# M1103A.net
KiCad netlist of a schematic drawn in EAGLE
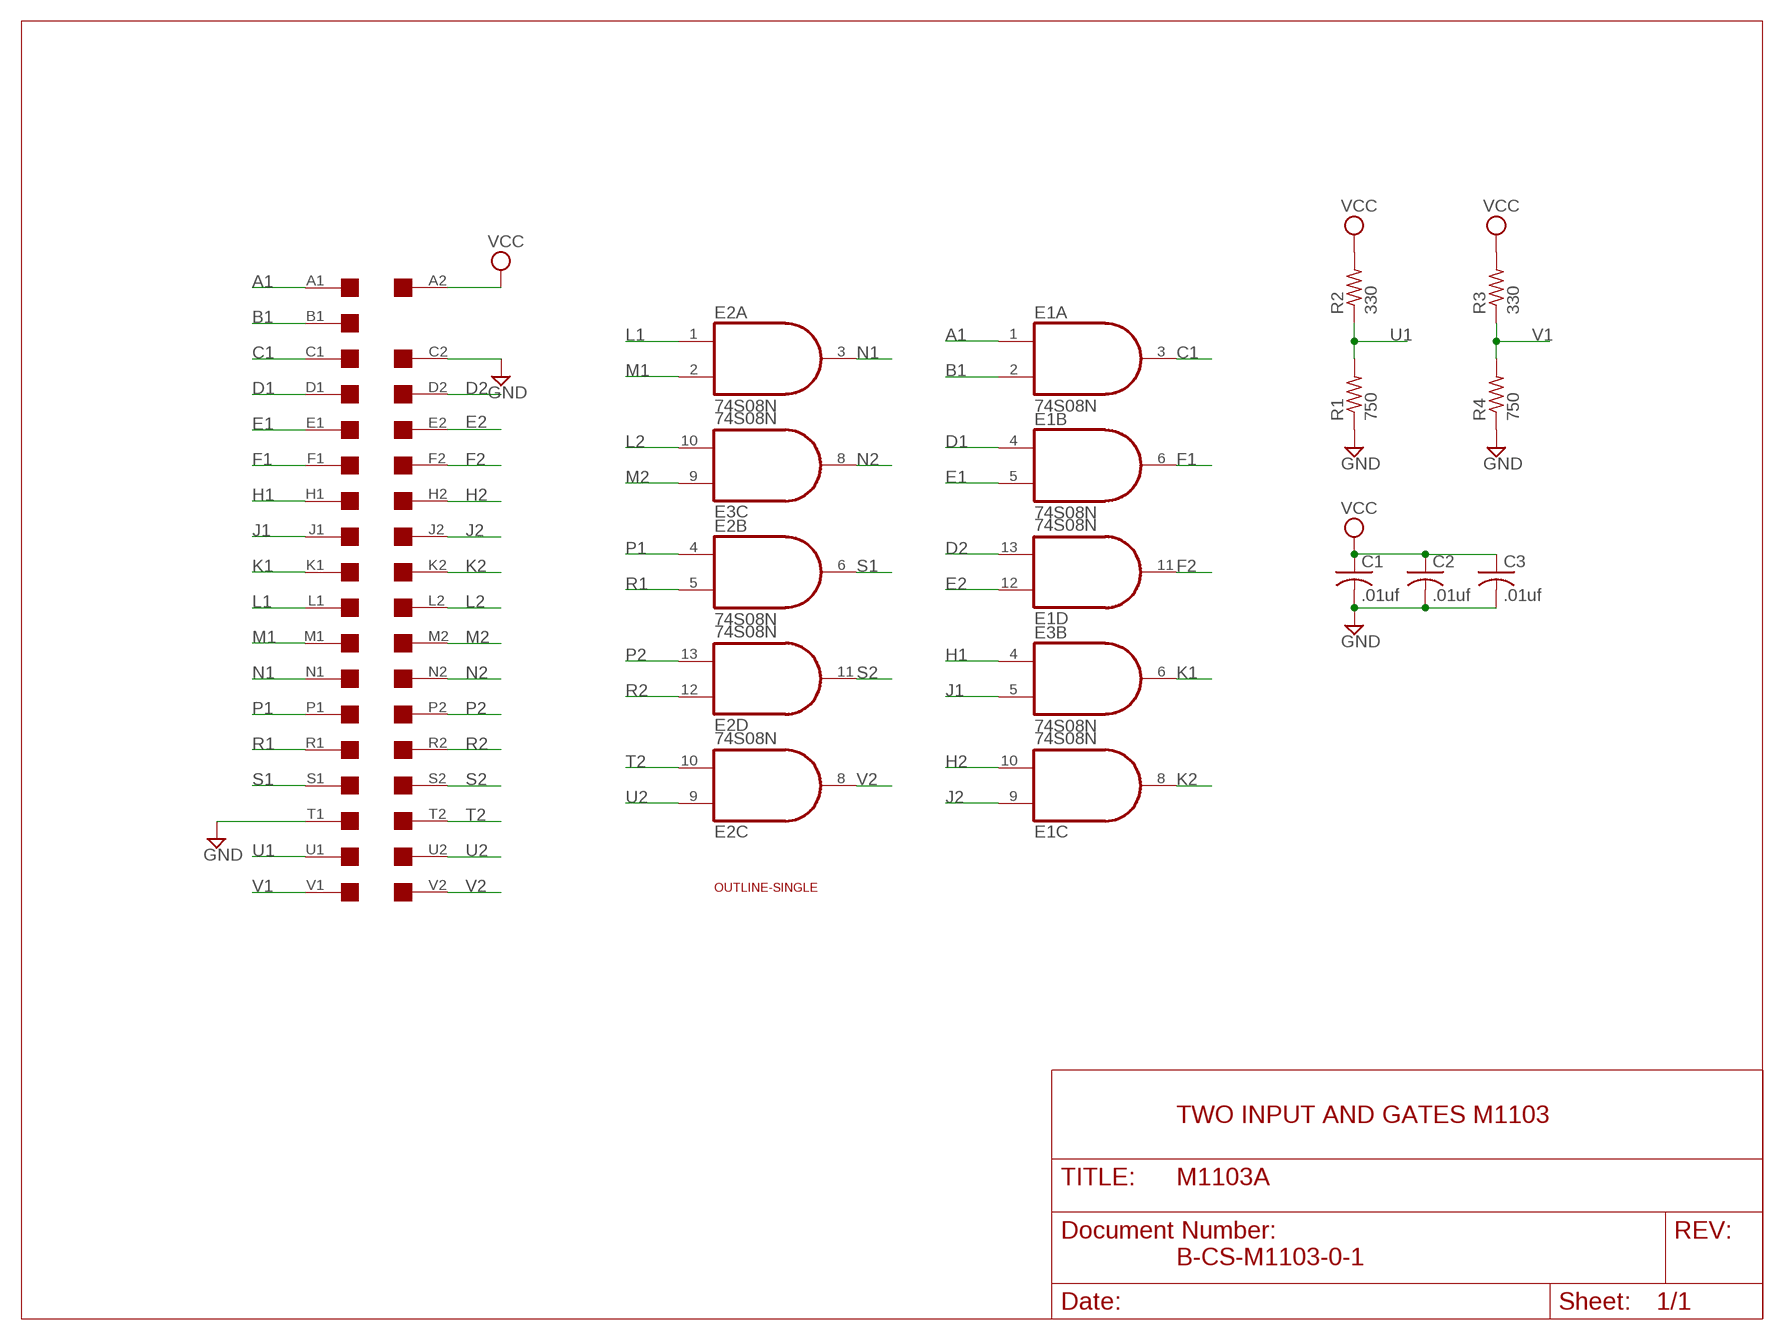
[diagram p0: schematic, sheet 1]

(export (version "E")
  (design (tool "Eeschema 10.0.6"))
  (components
    (comp (ref "C1")
      (value ".01uf")
      (footprint "eagle-import:C050-025X075")
      (libsource (lib "eagle-import") (part "C-US050-025X075"))
    )
    (comp (ref "C2")
      (value ".01uf")
      (footprint "eagle-import:C050-025X075")
      (libsource (lib "eagle-import") (part "C-US050-025X075"))
    )
    (comp (ref "C3")
      (value ".01uf")
      (footprint "eagle-import:C050-025X075")
      (libsource (lib "eagle-import") (part "C-US050-025X075"))
    )
    (comp (ref "E1")
      (value "74S08N")
      (footprint "eagle-import:DIL14")
      (libsource (lib "eagle-import") (part "7408NS"))
    )
    (comp (ref "E2")
      (value "74S08N")
      (footprint "eagle-import:DIL14")
      (libsource (lib "eagle-import") (part "7408NS"))
    )
    (comp (ref "E3")
      (value "74S08N")
      (footprint "eagle-import:DIL14")
      (libsource (lib "eagle-import") (part "7408NS"))
    )
    (comp (ref "R1")
      (value "750")
      (footprint "eagle-import:0207_10")
      (libsource (lib "eagle-import") (part "R-US_0207/10"))
    )
    (comp (ref "R2")
      (value "330")
      (footprint "eagle-import:0207_10")
      (libsource (lib "eagle-import") (part "R-US_0207/10"))
    )
    (comp (ref "R3")
      (value "330")
      (footprint "eagle-import:0207_10")
      (libsource (lib "eagle-import") (part "R-US_0207/10"))
    )
    (comp (ref "R4")
      (value "750")
      (footprint "eagle-import:0207_10")
      (libsource (lib "eagle-import") (part "R-US_0207/10"))
    )
    (comp (ref "U$1")
      (value "SINGLE")
      (footprint "eagle-import:EDGE-CON2")
      (libsource (lib "eagle-import") (part "SINGLE"))
    )
    (comp (ref "U$2")
      (value "OUTLINE-SINGLE")
      (footprint "eagle-import:SINGLE")
      (libsource (lib "eagle-import") (part "OUTLINE-SINGLE"))
    )
  )
  (nets
    (net (code "1") (name "/A1") (class "Default")
      (node (ref "E1") (pin "1") (pinfunction "I0_1") (pintype "input"))
      (node (ref "U$1") (pin "A1") (pinfunction "1_A1") (pintype "bidirectional"))
    )
    (net (code "2") (name "/B1") (class "Default")
      (node (ref "E1") (pin "2") (pinfunction "I1_2") (pintype "input"))
      (node (ref "U$1") (pin "B1") (pinfunction "1_B1") (pintype "bidirectional"))
    )
    (net (code "3") (name "/C1") (class "Default")
      (node (ref "E1") (pin "3") (pinfunction "O_3") (pintype "output"))
      (node (ref "U$1") (pin "C1") (pinfunction "1_C1") (pintype "bidirectional"))
    )
    (net (code "4") (name "/D1") (class "Default")
      (node (ref "E1") (pin "4") (pinfunction "I0_4") (pintype "input"))
      (node (ref "U$1") (pin "D1") (pinfunction "1_D1") (pintype "bidirectional"))
    )
    (net (code "5") (name "/D2") (class "Default")
      (node (ref "E1") (pin "13") (pinfunction "I1_13") (pintype "input"))
      (node (ref "U$1") (pin "D2") (pinfunction "1_D2") (pintype "bidirectional"))
    )
    (net (code "6") (name "/E1") (class "Default")
      (node (ref "E1") (pin "5") (pinfunction "I1_5") (pintype "input"))
      (node (ref "U$1") (pin "E1") (pinfunction "1_E1") (pintype "bidirectional"))
    )
    (net (code "7") (name "/E2") (class "Default")
      (node (ref "E1") (pin "12") (pinfunction "I0_12") (pintype "input"))
      (node (ref "U$1") (pin "E2") (pinfunction "1_E2") (pintype "bidirectional"))
    )
    (net (code "8") (name "/F1") (class "Default")
      (node (ref "E1") (pin "6") (pinfunction "O_6") (pintype "output"))
      (node (ref "U$1") (pin "F1") (pinfunction "1_F1") (pintype "bidirectional"))
    )
    (net (code "9") (name "/F2") (class "Default")
      (node (ref "E1") (pin "11") (pinfunction "O_11") (pintype "output"))
      (node (ref "U$1") (pin "F2") (pinfunction "1_F2") (pintype "bidirectional"))
    )
    (net (code "10") (name "/H1") (class "Default")
      (node (ref "E3") (pin "4") (pinfunction "I0_4") (pintype "input"))
      (node (ref "U$1") (pin "H1") (pinfunction "1_H1") (pintype "bidirectional"))
    )
    (net (code "11") (name "/H2") (class "Default")
      (node (ref "E1") (pin "10") (pinfunction "I1_10") (pintype "input"))
      (node (ref "U$1") (pin "H2") (pinfunction "1_H2") (pintype "bidirectional"))
    )
    (net (code "12") (name "/J1") (class "Default")
      (node (ref "E3") (pin "5") (pinfunction "I1_5") (pintype "input"))
      (node (ref "U$1") (pin "J1") (pinfunction "1_J1") (pintype "bidirectional"))
    )
    (net (code "13") (name "/J2") (class "Default")
      (node (ref "E1") (pin "9") (pinfunction "I0_9") (pintype "input"))
      (node (ref "U$1") (pin "J2") (pinfunction "1_J2") (pintype "bidirectional"))
    )
    (net (code "14") (name "/K1") (class "Default")
      (node (ref "E3") (pin "6") (pinfunction "O_6") (pintype "output"))
      (node (ref "U$1") (pin "K1") (pinfunction "1_K1") (pintype "bidirectional"))
    )
    (net (code "15") (name "/K2") (class "Default")
      (node (ref "E1") (pin "8") (pinfunction "O_8") (pintype "output"))
      (node (ref "U$1") (pin "K2") (pinfunction "1_K2") (pintype "bidirectional"))
    )
    (net (code "16") (name "/L1") (class "Default")
      (node (ref "E2") (pin "1") (pinfunction "I0_1") (pintype "input"))
      (node (ref "U$1") (pin "L1") (pinfunction "1_L1") (pintype "bidirectional"))
    )
    (net (code "17") (name "/L2") (class "Default")
      (node (ref "E3") (pin "10") (pinfunction "I1_10") (pintype "input"))
      (node (ref "U$1") (pin "L2") (pinfunction "1_L2") (pintype "bidirectional"))
    )
    (net (code "18") (name "/M1") (class "Default")
      (node (ref "E2") (pin "2") (pinfunction "I1_2") (pintype "input"))
      (node (ref "U$1") (pin "M1") (pinfunction "1_M1") (pintype "bidirectional"))
    )
    (net (code "19") (name "/M2") (class "Default")
      (node (ref "E3") (pin "9") (pinfunction "I0_9") (pintype "input"))
      (node (ref "U$1") (pin "M2") (pinfunction "1_M2") (pintype "bidirectional"))
    )
    (net (code "20") (name "/N1") (class "Default")
      (node (ref "E2") (pin "3") (pinfunction "O_3") (pintype "output"))
      (node (ref "U$1") (pin "N1") (pinfunction "1_N1") (pintype "bidirectional"))
    )
    (net (code "21") (name "/N2") (class "Default")
      (node (ref "E3") (pin "8") (pinfunction "O_8") (pintype "output"))
      (node (ref "U$1") (pin "N2") (pinfunction "1_N2") (pintype "bidirectional"))
    )
    (net (code "22") (name "/P1") (class "Default")
      (node (ref "E2") (pin "4") (pinfunction "I0_4") (pintype "input"))
      (node (ref "U$1") (pin "P1") (pinfunction "1_P1") (pintype "bidirectional"))
    )
    (net (code "23") (name "/P2") (class "Default")
      (node (ref "E2") (pin "13") (pinfunction "I1_13") (pintype "input"))
      (node (ref "U$1") (pin "P2") (pinfunction "1_P2") (pintype "bidirectional"))
    )
    (net (code "24") (name "/R1") (class "Default")
      (node (ref "E2") (pin "5") (pinfunction "I1_5") (pintype "input"))
      (node (ref "U$1") (pin "R1") (pinfunction "1_R1") (pintype "bidirectional"))
    )
    (net (code "25") (name "/R2") (class "Default")
      (node (ref "E2") (pin "12") (pinfunction "I0_12") (pintype "input"))
      (node (ref "U$1") (pin "R2") (pinfunction "1_R2") (pintype "bidirectional"))
    )
    (net (code "26") (name "/S1") (class "Default")
      (node (ref "E2") (pin "6") (pinfunction "O_6") (pintype "output"))
      (node (ref "U$1") (pin "S1") (pinfunction "1_S1") (pintype "bidirectional"))
    )
    (net (code "27") (name "/S2") (class "Default")
      (node (ref "E2") (pin "11") (pinfunction "O_11") (pintype "output"))
      (node (ref "U$1") (pin "S2") (pinfunction "1_S2") (pintype "bidirectional"))
    )
    (net (code "28") (name "/T2") (class "Default")
      (node (ref "E2") (pin "10") (pinfunction "I1_10") (pintype "input"))
      (node (ref "U$1") (pin "T2") (pinfunction "1_T2") (pintype "bidirectional"))
    )
    (net (code "29") (name "/U1") (class "Default")
      (node (ref "R1") (pin "2") (pinfunction "2_2") (pintype "passive"))
      (node (ref "R2") (pin "1") (pinfunction "1_1") (pintype "passive"))
      (node (ref "U$1") (pin "U1") (pinfunction "1_U1") (pintype "bidirectional"))
    )
    (net (code "30") (name "/U2") (class "Default")
      (node (ref "E2") (pin "9") (pinfunction "I0_9") (pintype "input"))
      (node (ref "U$1") (pin "U2") (pinfunction "1_U2") (pintype "bidirectional"))
    )
    (net (code "31") (name "/V1") (class "Default")
      (node (ref "R3") (pin "1") (pinfunction "1_1") (pintype "passive"))
      (node (ref "R4") (pin "2") (pinfunction "2_2") (pintype "passive"))
      (node (ref "U$1") (pin "V1") (pinfunction "1_V1") (pintype "bidirectional"))
    )
    (net (code "32") (name "/V2") (class "Default")
      (node (ref "E2") (pin "8") (pinfunction "O_8") (pintype "output"))
      (node (ref "U$1") (pin "V2") (pinfunction "1_V2") (pintype "bidirectional"))
    )
    (net (code "33") (name "GND") (class "Default")
      (node (ref "C1") (pin "2") (pinfunction "2_2") (pintype "passive"))
      (node (ref "C2") (pin "2") (pinfunction "2_2") (pintype "passive"))
      (node (ref "C3") (pin "2") (pinfunction "2_2") (pintype "passive"))
      (node (ref "R1") (pin "1") (pinfunction "1_1") (pintype "passive"))
      (node (ref "R4") (pin "1") (pinfunction "1_1") (pintype "passive"))
      (node (ref "U$1") (pin "C2") (pinfunction "1_C2") (pintype "bidirectional"))
      (node (ref "U$1") (pin "T1") (pinfunction "1_T1") (pintype "bidirectional"))
    )
    (net (code "34") (name "VCC") (class "Default")
      (node (ref "C1") (pin "1") (pinfunction "1_1") (pintype "passive"))
      (node (ref "C2") (pin "1") (pinfunction "1_1") (pintype "passive"))
      (node (ref "C3") (pin "1") (pinfunction "1_1") (pintype "passive"))
      (node (ref "R2") (pin "2") (pinfunction "2_2") (pintype "passive"))
      (node (ref "R3") (pin "2") (pinfunction "2_2") (pintype "passive"))
      (node (ref "U$1") (pin "A2") (pinfunction "1_A2") (pintype "bidirectional"))
    )
  )
)
